# DA14580.net
KiCad netlist of a schematic drawn in Altium Designer
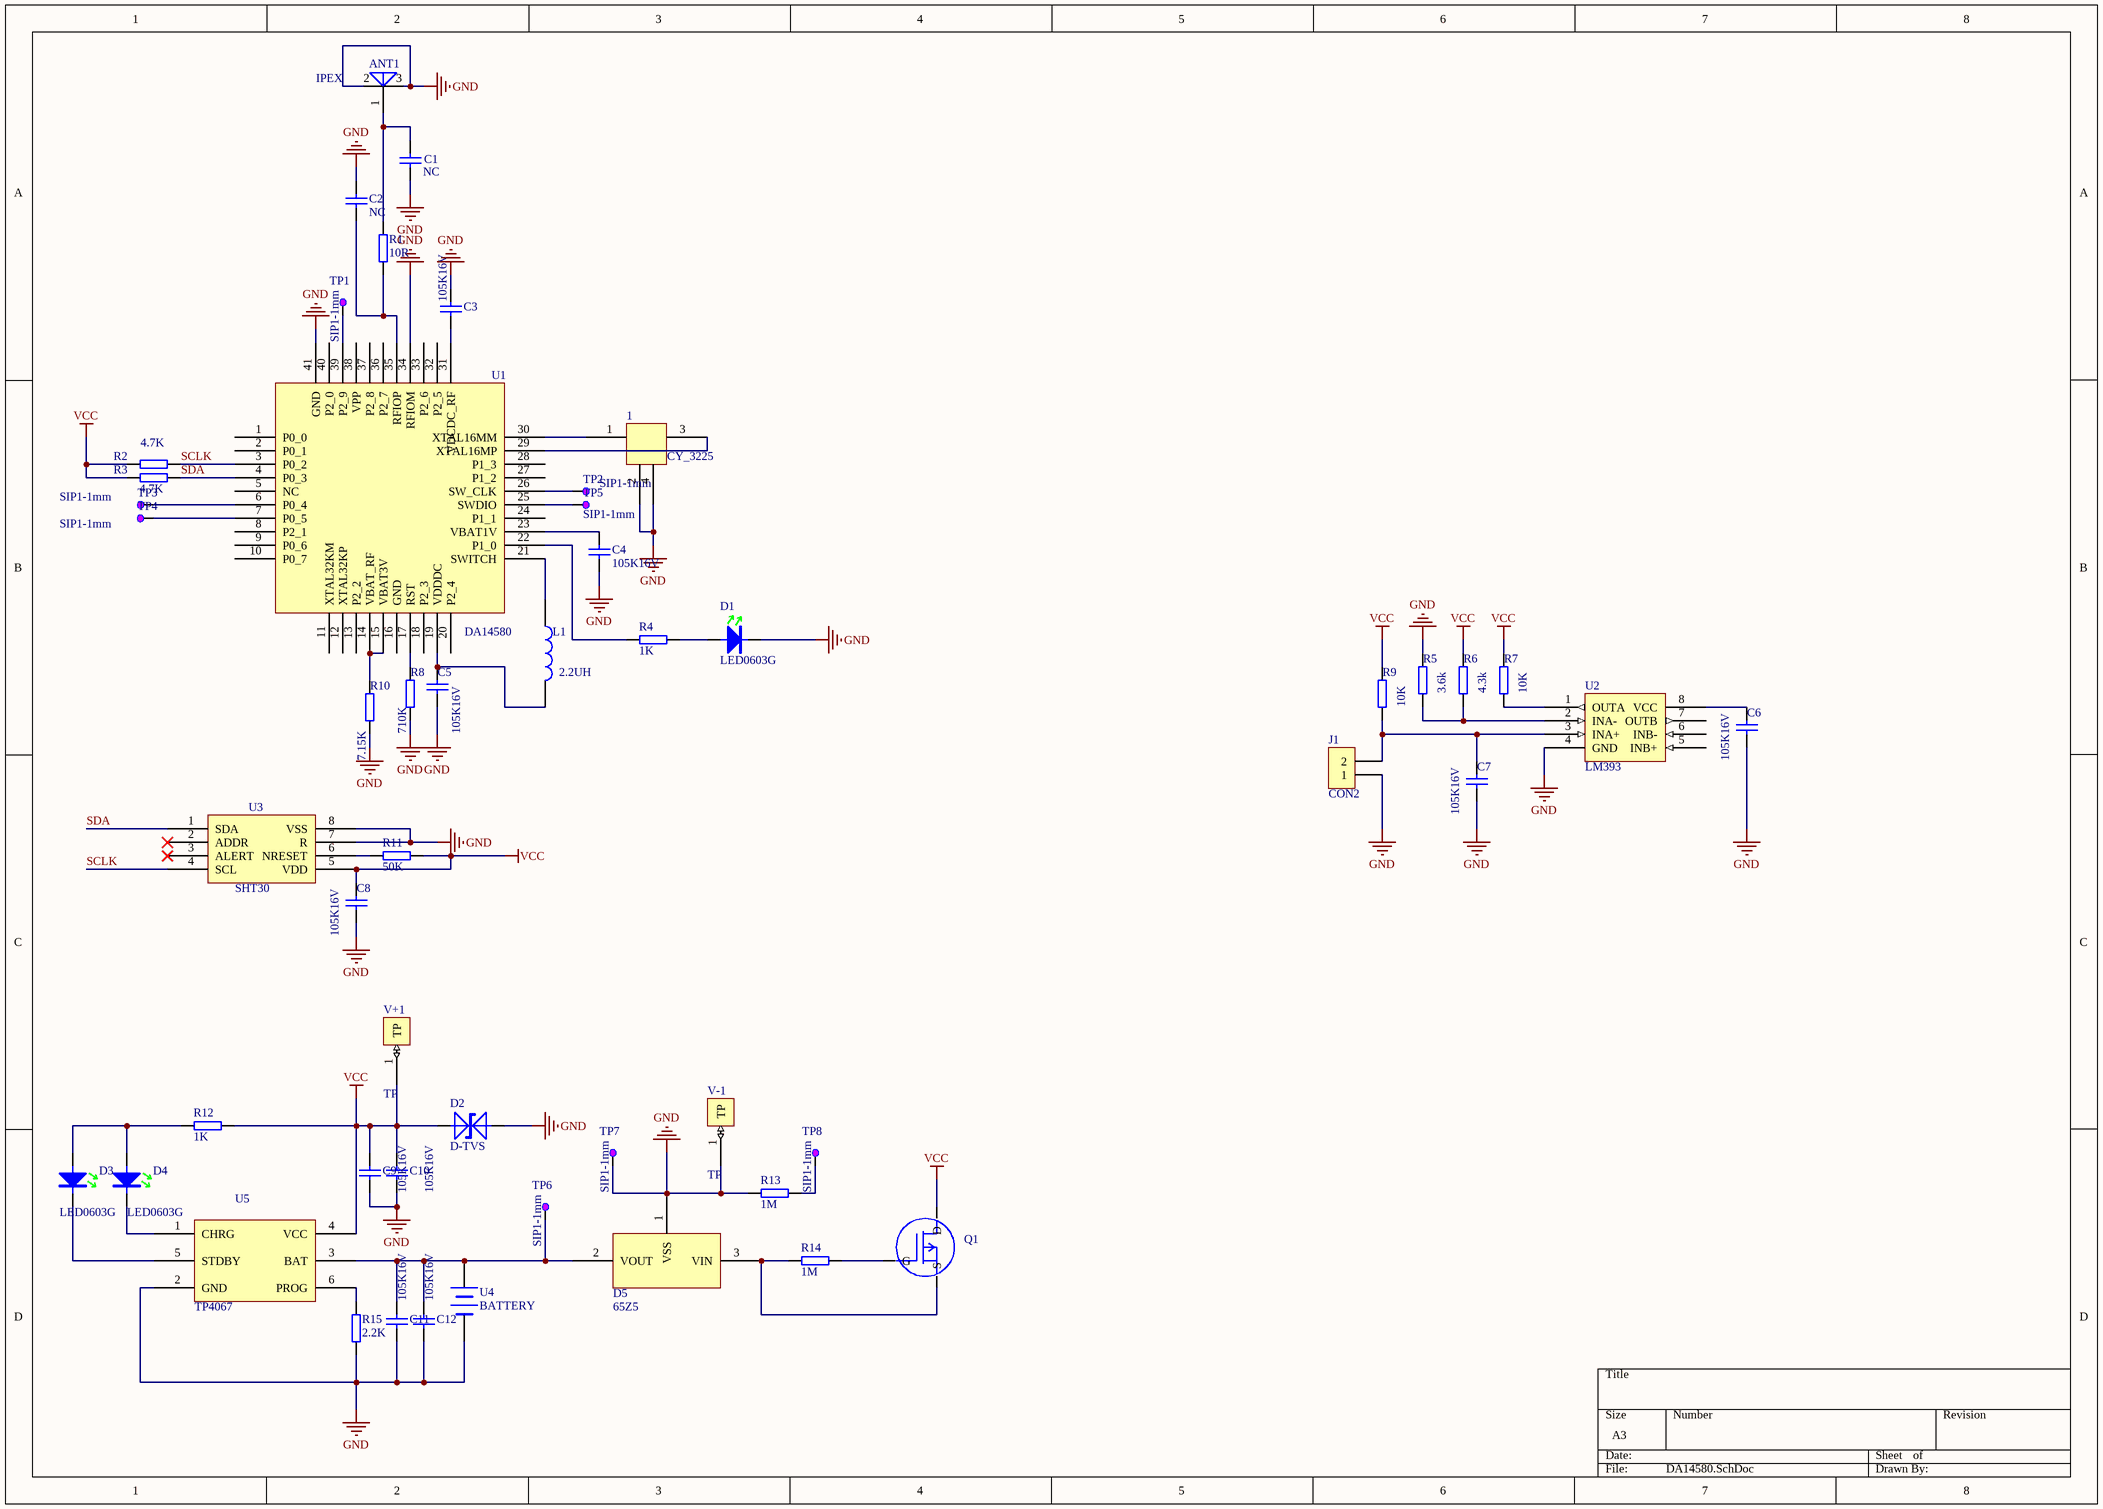
[diagram p0: DA14580.SchDoc]

(export (version "E")
  (design (tool "Eeschema 10.0.6"))
  (components
    (comp (ref "1")
      (value "CY_3225")
      (footprint "CY_3225")
      (libsource (lib "AIWAC-bolsterV01") (part "CY_3225"))
    )
    (comp (ref "ANT1") (value "IPEX") (footprint "IFA") (libsource (lib "AIWAC-bolsterV01") (part "J-IPEX")))
    (comp (ref "C1")
      (value "NC")
      (footprint "C0402")
      (description "贴片电容-陶瓷")
      (libsource (lib "AIWAC-bolsterV01") (part "C0402X7R-101J10V"))
    )
    (comp (ref "C2")
      (value "NC")
      (footprint "C0402")
      (description "贴片电容-陶瓷")
      (libsource (lib "AIWAC-bolsterV01") (part "C0402X7R-101J10V"))
    )
    (comp (ref "C3")
      (value "105K16V")
      (footprint "C0603")
      (description "贴片电容-陶瓷")
      (libsource (lib "AIWAC-bolsterV01") (part "C0603X7R-105K16V"))
    )
    (comp (ref "C4")
      (value "105K16V")
      (footprint "C0603")
      (description "贴片电容-陶瓷")
      (libsource (lib "AIWAC-bolsterV01") (part "C0603X7R-105K16V"))
    )
    (comp (ref "C5")
      (value "105K16V")
      (footprint "C0603")
      (description "贴片电容-陶瓷")
      (libsource (lib "AIWAC-bolsterV01") (part "C0603X7R-105K16V"))
    )
    (comp (ref "C6")
      (value "105K16V")
      (footprint "C0603")
      (description "贴片电容-陶瓷")
      (libsource (lib "AIWAC-bolsterV01") (part "C0603X7R-105K16V"))
    )
    (comp (ref "C7")
      (value "105K16V")
      (footprint "C0603")
      (description "贴片电容-陶瓷")
      (libsource (lib "AIWAC-bolsterV01") (part "C0603X7R-105K16V"))
    )
    (comp (ref "C8")
      (value "105K16V")
      (footprint "C0603")
      (description "贴片电容-陶瓷")
      (libsource (lib "AIWAC-bolsterV01") (part "C0603X7R-105K16V"))
    )
    (comp (ref "C9")
      (value "105K16V")
      (footprint "C0603")
      (description "贴片电容-陶瓷")
      (libsource (lib "AIWAC-bolsterV01") (part "C0603X7R-105K16V"))
    )
    (comp (ref "C10")
      (value "105K16V")
      (footprint "C0603")
      (description "贴片电容-陶瓷")
      (libsource (lib "AIWAC-bolsterV01") (part "C0603X7R-105K16V"))
    )
    (comp (ref "C11")
      (value "105K16V")
      (footprint "C0603")
      (description "贴片电容-陶瓷")
      (libsource (lib "AIWAC-bolsterV01") (part "C0603X7R-105K16V"))
    )
    (comp (ref "C12")
      (value "105K16V")
      (footprint "C0603")
      (description "贴片电容-陶瓷")
      (libsource (lib "AIWAC-bolsterV01") (part "C0603X7R-105K16V"))
    )
    (comp (ref "D1")
      (value "LED0603G")
      (footprint "HS_0603D")
      (description "贴片二极管-LED")
      (libsource (lib "AIWAC-bolsterV01") (part "DLED-0603-G"))
    )
    (comp (ref "D2") (value "D-TVS") (footprint "0603C") (libsource (lib "XU-GENARAL SCH") (part "D-TVS")))
    (comp (ref "D3")
      (value "LED0603G")
      (footprint "HS_0603D")
      (description "贴片二极管-LED")
      (libsource (lib "AIWAC-bolsterV01") (part "DLED-0603-G"))
    )
    (comp (ref "D4")
      (value "LED0603G")
      (footprint "HS_0603D")
      (description "贴片二极管-LED")
      (libsource (lib "AIWAC-bolsterV01") (part "DLED-0603-G"))
    )
    (comp (ref "D5")
      (value "65Z5")
      (footprint "U-SOT-23-3")
      (libsource (lib "AIWAC-bolsterV01") (part "65Z5"))
    )
    (comp (ref "J1")
      (value "CON2")
      (footprint "J-SH1.0-T-1-LT-2A")
      (description "Connector")
      (libsource (lib "AIWAC-bolsterV01") (part "CON2"))
    )
    (comp (ref "L1")
      (value "2.2UH")
      (footprint "0805")
      (libsource (lib "AIWAC-bolsterV01") (part "INDUCTOR"))
    )
    (comp (ref "Q1")
      (value "AO3401 SOT-23")
      (footprint "SOT23-AO3401")
      (description "MOS管")
      (libsource (lib "AIWAC-bolsterV01") (part "2321 SOT-23"))
    )
    (comp (ref "R1")
      (value "10R")
      (footprint "R0402")
      (description "贴片电阻-通用")
      (libsource (lib "AIWAC-bolsterV01") (part "R0402-1KF"))
    )
    (comp (ref "R2")
      (value "4.7K")
      (footprint "R0402")
      (description "贴片电阻-通用")
      (libsource (lib "AIWAC-bolsterV01") (part "R0402-1KF"))
    )
    (comp (ref "R3")
      (value "4.7K")
      (footprint "R0402")
      (description "贴片电阻-通用")
      (libsource (lib "AIWAC-bolsterV01") (part "R0402-1KF"))
    )
    (comp (ref "R4")
      (value "1K")
      (footprint "R0402")
      (description "贴片电阻-通用")
      (libsource (lib "AIWAC-bolsterV01") (part "R0402-1KF"))
    )
    (comp (ref "R5")
      (value "3.6k")
      (footprint "R0402")
      (description "贴片电阻-通用")
      (libsource (lib "AIWAC-bolsterV01") (part "R0402-1KF"))
    )
    (comp (ref "R6")
      (value "4.3k")
      (footprint "R0402")
      (description "贴片电阻-通用")
      (libsource (lib "AIWAC-bolsterV01") (part "R0402-1KF"))
    )
    (comp (ref "R7")
      (value "10K")
      (footprint "R0402")
      (description "贴片电阻-通用")
      (libsource (lib "AIWAC-bolsterV01") (part "R0402-1KF"))
    )
    (comp (ref "R8")
      (value "710K")
      (footprint "R0402")
      (description "贴片电阻-通用")
      (libsource (lib "AIWAC-bolsterV01") (part "R0402-1KF"))
    )
    (comp (ref "R9")
      (value "10K")
      (footprint "R0402")
      (description "贴片电阻-通用")
      (libsource (lib "AIWAC-bolsterV01") (part "R0402-1KF"))
    )
    (comp (ref "R10")
      (value "7.15K")
      (footprint "R0402")
      (description "贴片电阻-通用")
      (libsource (lib "AIWAC-bolsterV01") (part "R0402-1KF"))
    )
    (comp (ref "R11")
      (value "50K")
      (footprint "R0402")
      (description "贴片电阻-通用")
      (libsource (lib "AIWAC-bolsterV01") (part "R0402-1KF"))
    )
    (comp (ref "R12")
      (value "1K")
      (footprint "R0402")
      (description "贴片电阻-通用")
      (libsource (lib "AIWAC-bolsterV01") (part "R0402-1KF"))
    )
    (comp (ref "R13")
      (value "1M")
      (footprint "R0402")
      (description "贴片电阻-通用")
      (libsource (lib "AIWAC-bolsterV01") (part "R0402-1KF"))
    )
    (comp (ref "R14")
      (value "1M")
      (footprint "R0402")
      (description "贴片电阻-通用")
      (libsource (lib "AIWAC-bolsterV01") (part "R0402-1KF"))
    )
    (comp (ref "R15")
      (value "2.2K")
      (footprint "R0402")
      (description "贴片电阻-通用")
      (libsource (lib "AIWAC-bolsterV01") (part "R0402-1KF"))
    )
    (comp (ref "TP1")
      (value "SIP1-1mm")
      (footprint "SIP - 1MM")
      (libsource (lib "AIWAC-bolsterV01") (part "SIP1-2mm"))
    )
    (comp (ref "TP2")
      (value "SIP1-1mm")
      (footprint "SIP - 1MM")
      (libsource (lib "AIWAC-bolsterV01") (part "SIP1-2mm"))
    )
    (comp (ref "TP3")
      (value "SIP1-1mm")
      (footprint "SIP - 1MM")
      (libsource (lib "AIWAC-bolsterV01") (part "SIP1-2mm"))
    )
    (comp (ref "TP4")
      (value "SIP1-1mm")
      (footprint "SIP - 1MM")
      (libsource (lib "AIWAC-bolsterV01") (part "SIP1-2mm"))
    )
    (comp (ref "TP5")
      (value "SIP1-1mm")
      (footprint "SIP - 1MM")
      (libsource (lib "AIWAC-bolsterV01") (part "SIP1-2mm"))
    )
    (comp (ref "TP6")
      (value "SIP1-1mm")
      (footprint "SIP - 1MM")
      (libsource (lib "AIWAC-bolsterV01") (part "SIP1-2mm"))
    )
    (comp (ref "TP7")
      (value "SIP1-1mm")
      (footprint "SIP - 1MM")
      (libsource (lib "AIWAC-bolsterV01") (part "SIP1-2mm"))
    )
    (comp (ref "TP8")
      (value "SIP1-1mm")
      (footprint "SIP - 1MM")
      (libsource (lib "AIWAC-bolsterV01") (part "SIP1-2mm"))
    )
    (comp (ref "U1")
      (value "DA14580")
      (footprint "QFN40P500*500_HS-41N")
      (description "bluetooth")
      (libsource (lib "AIWAC-bolsterV01") (part "DA14580"))
    )
    (comp (ref "U2") (value "LM393") (footprint "SO-8S") (libsource (lib "AIWAC-bolsterV01") (part "LM393")))
    (comp (ref "U3")
      (value "SHT30")
      (footprint "SHT30 DL7DV9")
      (libsource (lib "AIWAC-bolsterV01") (part "SHT30"))
    )
    (comp (ref "U4")
      (value "BATTERY")
      (footprint "BAT 4mm")
      (libsource (lib "HSC32K1(QFN56)_BlueTooth_V2.0_20171108 - 副本") (part "BATTERY"))
    )
    (comp (ref "U5")
      (value "TP4067")
      (footprint "SOT23-6")
      (libsource (lib "AIWAC-bolsterV01") (part "TP4067"))
    )
    (comp (ref "V+1") (value "TP") (footprint "SIP-2MM") (libsource (lib "AIWAC-bolsterV01") (part "TP")))
    (comp (ref "V-1") (value "TP") (footprint "SIP-2MM") (libsource (lib "AIWAC-bolsterV01") (part "TP")))
  )
  (nets
    (net (code "1") (name "/SCLK") (class "Default")
      (node (ref "R2") (pin "1") (pinfunction "1_1") (pintype "passive"))
      (node (ref "U1") (pin "3") (pinfunction "P0_2_3") (pintype "passive"))
      (node (ref "U3") (pin "4") (pinfunction "SCL_4") (pintype "passive"))
    )
    (net (code "2") (name "/SDA") (class "Default")
      (node (ref "R3") (pin "1") (pinfunction "1_1") (pintype "passive"))
      (node (ref "U1") (pin "4") (pinfunction "P0_3_4") (pintype "passive"))
      (node (ref "U3") (pin "1") (pinfunction "SDA_1") (pintype "passive"))
    )
    (net (code "3") (name "GND") (class "Default")
      (node (ref "1") (pin "2") (pinfunction "2_2") (pintype "power_in"))
      (node (ref "1") (pin "4") (pinfunction "4_4") (pintype "power_in"))
      (node (ref "ANT1") (pin "2") (pinfunction "2_2") (pintype "passive"))
      (node (ref "ANT1") (pin "3") (pinfunction "3_3") (pintype "passive"))
      (node (ref "C1") (pin "2") (pinfunction "2_2") (pintype "passive"))
      (node (ref "C10") (pin "2") (pinfunction "2_2") (pintype "passive"))
      (node (ref "C11") (pin "2") (pinfunction "2_2") (pintype "passive"))
      (node (ref "C12") (pin "2") (pinfunction "2_2") (pintype "passive"))
      (node (ref "C2") (pin "1") (pinfunction "1_1") (pintype "passive"))
      (node (ref "C3") (pin "1") (pinfunction "1_1") (pintype "passive"))
      (node (ref "C4") (pin "2") (pinfunction "2_2") (pintype "passive"))
      (node (ref "C5") (pin "2") (pinfunction "2_2") (pintype "passive"))
      (node (ref "C6") (pin "2") (pinfunction "2_2") (pintype "passive"))
      (node (ref "C7") (pin "2") (pinfunction "2_2") (pintype "passive"))
      (node (ref "C8") (pin "2") (pinfunction "2_2") (pintype "passive"))
      (node (ref "C9") (pin "2") (pinfunction "2_2") (pintype "passive"))
      (node (ref "D1") (pin "2") (pinfunction "2_2") (pintype "passive"))
      (node (ref "D2") (pin "1") (pintype "passive"))
      (node (ref "D5") (pin "1") (pinfunction "VSS_1") (pintype "passive"))
      (node (ref "J1") (pin "1") (pinfunction "1_1") (pintype "passive"))
      (node (ref "R10") (pin "1") (pinfunction "1_1") (pintype "passive"))
      (node (ref "R13") (pin "1") (pinfunction "1_1") (pintype "passive"))
      (node (ref "R15") (pin "1") (pinfunction "1_1") (pintype "passive"))
      (node (ref "R5") (pin "2") (pinfunction "2_2") (pintype "passive"))
      (node (ref "R8") (pin "1") (pinfunction "1_1") (pintype "passive"))
      (node (ref "TP7") (pin "1") (pinfunction "1_1") (pintype "passive"))
      (node (ref "U1") (pin "34") (pinfunction "RFIOM_34") (pintype "passive"))
      (node (ref "U1") (pin "41") (pinfunction "GND_41") (pintype "passive"))
      (node (ref "U2") (pin "4") (pinfunction "GND_4") (pintype "power_in"))
      (node (ref "U3") (pin "7") (pinfunction "R_7") (pintype "passive"))
      (node (ref "U3") (pin "8") (pinfunction "VSS_8") (pintype "passive"))
      (node (ref "U4") (pin "2") (pinfunction "-_2") (pintype "passive"))
      (node (ref "U5") (pin "2") (pinfunction "GND_2") (pintype "passive"))
      (node (ref "V-1") (pin "1") (pinfunction "TP_1") (pintype "bidirectional"))
    )
    (net (code "4") (name "Net-(ANT1-W)") (class "Default")
      (node (ref "ANT1") (pin "1") (pinfunction "W_1") (pintype "passive"))
      (node (ref "C1") (pin "1") (pinfunction "1_1") (pintype "passive"))
      (node (ref "R1") (pin "1") (pinfunction "1_1") (pintype "passive"))
    )
    (net (code "5") (name "Net-(D1-Pad1)") (class "Default")
      (node (ref "D1") (pin "1") (pinfunction "1_1") (pintype "passive"))
      (node (ref "R4") (pin "2") (pinfunction "2_2") (pintype "passive"))
    )
    (net (code "6") (name "Net-(D3-Pad1)") (class "Default")
      (node (ref "D3") (pin "1") (pinfunction "1_1") (pintype "passive"))
      (node (ref "D4") (pin "1") (pinfunction "1_1") (pintype "passive"))
      (node (ref "R12") (pin "1") (pinfunction "1_1") (pintype "passive"))
    )
    (net (code "7") (name "Net-(D5-VIN)") (class "Default")
      (node (ref "D5") (pin "3") (pinfunction "VIN_3") (pintype "passive"))
      (node (ref "Q1") (pin "S") (pinfunction "S_S") (pintype "passive"))
      (node (ref "R14") (pin "1") (pinfunction "1_1") (pintype "passive"))
    )
    (net (code "8") (name "Net-(D5-VOUT)") (class "Default")
      (node (ref "C11") (pin "1") (pinfunction "1_1") (pintype "passive"))
      (node (ref "C12") (pin "1") (pinfunction "1_1") (pintype "passive"))
      (node (ref "D5") (pin "2") (pinfunction "VOUT_2") (pintype "passive"))
      (node (ref "TP6") (pin "1") (pinfunction "1_1") (pintype "passive"))
      (node (ref "U4") (pin "1") (pinfunction "+_1") (pintype "passive"))
      (node (ref "U5") (pin "3") (pinfunction "BAT_3") (pintype "passive"))
    )
    (net (code "9") (name "Net-(Q1-PadG)") (class "Default")
      (node (ref "Q1") (pin "G") (pinfunction "G_G") (pintype "passive"))
      (node (ref "R14") (pin "2") (pinfunction "2_2") (pintype "passive"))
    )
    (net (code "10") (name "Net-(R13-Pad2)") (class "Default")
      (node (ref "R13") (pin "2") (pinfunction "2_2") (pintype "passive"))
      (node (ref "TP8") (pin "1") (pinfunction "1_1") (pintype "passive"))
    )
    (net (code "11") (name "Net-(U1-P0_4)") (class "Default")
      (node (ref "TP3") (pin "1") (pinfunction "1_1") (pintype "passive"))
      (node (ref "U1") (pin "6") (pinfunction "P0_4_6") (pintype "passive"))
    )
    (net (code "12") (name "Net-(U1-P0_5)") (class "Default")
      (node (ref "TP4") (pin "1") (pinfunction "1_1") (pintype "passive"))
      (node (ref "U1") (pin "7") (pinfunction "P0_5_7") (pintype "passive"))
    )
    (net (code "13") (name "Net-(U1-P1_0)") (class "Default")
      (node (ref "R4") (pin "1") (pinfunction "1_1") (pintype "passive"))
      (node (ref "U1") (pin "22") (pinfunction "P1_0_22") (pintype "passive"))
    )
    (net (code "14") (name "Net-(U1-P2_9)") (class "Default")
      (node (ref "TP1") (pin "1") (pinfunction "1_1") (pintype "passive"))
      (node (ref "U1") (pin "39") (pinfunction "P2_9_39") (pintype "passive"))
    )
    (net (code "15") (name "Net-(U1-RFIOP)") (class "Default")
      (node (ref "C2") (pin "2") (pinfunction "2_2") (pintype "passive"))
      (node (ref "R1") (pin "2") (pinfunction "2_2") (pintype "passive"))
      (node (ref "U1") (pin "35") (pinfunction "RFIOP_35") (pintype "passive"))
    )
    (net (code "16") (name "Net-(U1-RST)") (class "Default")
      (node (ref "R8") (pin "2") (pinfunction "2_2") (pintype "passive"))
      (node (ref "U1") (pin "17") (pinfunction "RST_17") (pintype "passive"))
    )
    (net (code "17") (name "Net-(U1-SWDIO)") (class "Default")
      (node (ref "TP5") (pin "1") (pinfunction "1_1") (pintype "passive"))
      (node (ref "U1") (pin "25") (pinfunction "SWDIO_25") (pintype "passive"))
    )
    (net (code "18") (name "Net-(U1-SWITCH)") (class "Default")
      (node (ref "L1") (pin "1") (pinfunction "1_1") (pintype "passive"))
      (node (ref "U1") (pin "21") (pinfunction "SWITCH_21") (pintype "passive"))
    )
    (net (code "19") (name "Net-(U1-SW_CLK)") (class "Default")
      (node (ref "TP2") (pin "1") (pinfunction "1_1") (pintype "passive"))
      (node (ref "U1") (pin "26") (pinfunction "SW_CLK_26") (pintype "passive"))
    )
    (net (code "20") (name "Net-(U1-VBAT1V)") (class "Default")
      (node (ref "C4") (pin "1") (pinfunction "1_1") (pintype "passive"))
      (node (ref "U1") (pin "23") (pinfunction "VBAT1V_23") (pintype "passive"))
    )
    (net (code "21") (name "Net-(U1-VBAT3V)") (class "Default")
      (node (ref "R10") (pin "2") (pinfunction "2_2") (pintype "passive"))
      (node (ref "U1") (pin "14") (pinfunction "VBAT_RF_14") (pintype "passive"))
      (node (ref "U1") (pin "15") (pinfunction "VBAT3V_15") (pintype "passive"))
    )
    (net (code "22") (name "Net-(U1-VDCDC_RF)") (class "Default")
      (node (ref "C3") (pin "2") (pinfunction "2_2") (pintype "passive"))
      (node (ref "U1") (pin "31") (pinfunction "VDCDC_RF_31") (pintype "passive"))
    )
    (net (code "23") (name "Net-(U1-VDDDC)") (class "Default")
      (node (ref "C5") (pin "1") (pinfunction "1_1") (pintype "passive"))
      (node (ref "L1") (pin "2") (pinfunction "2_2") (pintype "passive"))
      (node (ref "U1") (pin "19") (pinfunction "VDDDC_19") (pintype "passive"))
    )
    (net (code "24") (name "Net-(U1-XTAL16MM)") (class "Default")
      (node (ref "1") (pin "1") (pinfunction "1_1") (pintype "power_in"))
      (node (ref "U1") (pin "30") (pinfunction "XTAL16MM_30") (pintype "passive"))
    )
    (net (code "25") (name "Net-(U1-XTAL16MP)") (class "Default")
      (node (ref "1") (pin "3") (pinfunction "3_3") (pintype "power_in"))
      (node (ref "U1") (pin "29") (pinfunction "XTAL16MP_29") (pintype "passive"))
    )
    (net (code "26") (name "Net-(U2-INA+)") (class "Default")
      (node (ref "C7") (pin "1") (pinfunction "1_1") (pintype "passive"))
      (node (ref "J1") (pin "2") (pinfunction "2_2") (pintype "passive"))
      (node (ref "R9") (pin "1") (pinfunction "1_1") (pintype "passive"))
      (node (ref "U2") (pin "3") (pinfunction "INA+_3") (pintype "input"))
    )
    (net (code "27") (name "Net-(U2-INA-)") (class "Default")
      (node (ref "R5") (pin "1") (pinfunction "1_1") (pintype "passive"))
      (node (ref "R6") (pin "1") (pinfunction "1_1") (pintype "passive"))
      (node (ref "U2") (pin "2") (pinfunction "INA-_2") (pintype "input"))
    )
    (net (code "28") (name "Net-(U2-OUTA)") (class "Default")
      (node (ref "R7") (pin "1") (pinfunction "1_1") (pintype "passive"))
      (node (ref "U2") (pin "1") (pinfunction "OUTA_1") (pintype "output"))
    )
    (net (code "29") (name "Net-(U2-VCC)") (class "Default")
      (node (ref "C6") (pin "1") (pinfunction "1_1") (pintype "passive"))
      (node (ref "U2") (pin "8") (pinfunction "VCC_8") (pintype "power_in"))
    )
    (net (code "30") (name "Net-(U3-NRESET)") (class "Default")
      (node (ref "R11") (pin "1") (pinfunction "1_1") (pintype "passive"))
      (node (ref "U3") (pin "6") (pinfunction "NRESET_6") (pintype "passive"))
    )
    (net (code "31") (name "Net-(U5-CHRG)") (class "Default")
      (node (ref "D4") (pin "2") (pinfunction "2_2") (pintype "passive"))
      (node (ref "U5") (pin "1") (pinfunction "CHRG_1") (pintype "passive"))
    )
    (net (code "32") (name "Net-(U5-PROG)") (class "Default")
      (node (ref "R15") (pin "2") (pinfunction "2_2") (pintype "passive"))
      (node (ref "U5") (pin "6") (pinfunction "PROG_6") (pintype "passive"))
    )
    (net (code "33") (name "Net-(U5-STDBY)") (class "Default")
      (node (ref "D3") (pin "2") (pinfunction "2_2") (pintype "passive"))
      (node (ref "U5") (pin "5") (pinfunction "STDBY_5") (pintype "passive"))
    )
    (net (code "34") (name "VCC") (class "Default")
      (node (ref "C10") (pin "1") (pinfunction "1_1") (pintype "passive"))
      (node (ref "C8") (pin "1") (pinfunction "1_1") (pintype "passive"))
      (node (ref "C9") (pin "1") (pinfunction "1_1") (pintype "passive"))
      (node (ref "D2") (pin "2") (pintype "passive"))
      (node (ref "Q1") (pin "D") (pinfunction "D_D") (pintype "passive"))
      (node (ref "R11") (pin "2") (pinfunction "2_2") (pintype "passive"))
      (node (ref "R12") (pin "2") (pinfunction "2_2") (pintype "passive"))
      (node (ref "R2") (pin "2") (pinfunction "2_2") (pintype "passive"))
      (node (ref "R3") (pin "2") (pinfunction "2_2") (pintype "passive"))
      (node (ref "R6") (pin "2") (pinfunction "2_2") (pintype "passive"))
      (node (ref "R7") (pin "2") (pinfunction "2_2") (pintype "passive"))
      (node (ref "R9") (pin "2") (pinfunction "2_2") (pintype "passive"))
      (node (ref "U3") (pin "5") (pinfunction "VDD_5") (pintype "passive"))
      (node (ref "U5") (pin "4") (pinfunction "VCC_4") (pintype "passive"))
      (node (ref "V+1") (pin "1") (pinfunction "TP_1") (pintype "bidirectional"))
    )
    (net (code "35") (name "unconnected-(U1-GND-Pad16)") (class "Default")
      (node (ref "U1") (pin "16") (pinfunction "GND_16") (pintype "passive"))
    )
    (net (code "36") (name "unconnected-(U1-NC-Pad5)") (class "Default")
      (node (ref "U1") (pin "5") (pinfunction "NC_5") (pintype "passive"))
    )
    (net (code "37") (name "unconnected-(U1-P0_0-Pad1)") (class "Default")
      (node (ref "U1") (pin "1") (pinfunction "P0_0_1") (pintype "passive"))
    )
    (net (code "38") (name "unconnected-(U1-P0_1-Pad2)") (class "Default")
      (node (ref "U1") (pin "2") (pinfunction "P0_1_2") (pintype "passive"))
    )
    (net (code "39") (name "unconnected-(U1-P0_6-Pad9)") (class "Default")
      (node (ref "U1") (pin "9") (pinfunction "P0_6_9") (pintype "passive"))
    )
    (net (code "40") (name "unconnected-(U1-P0_7-Pad10)") (class "Default")
      (node (ref "U1") (pin "10") (pinfunction "P0_7_10") (pintype "passive"))
    )
    (net (code "41") (name "unconnected-(U1-P1_1-Pad24)") (class "Default")
      (node (ref "U1") (pin "24") (pinfunction "P1_1_24") (pintype "passive"))
    )
    (net (code "42") (name "unconnected-(U1-P1_2-Pad27)") (class "Default")
      (node (ref "U1") (pin "27") (pinfunction "P1_2_27") (pintype "passive"))
    )
    (net (code "43") (name "unconnected-(U1-P1_3-Pad28)") (class "Default")
      (node (ref "U1") (pin "28") (pinfunction "P1_3_28") (pintype "passive"))
    )
    (net (code "44") (name "unconnected-(U1-P2_0-Pad40)") (class "Default")
      (node (ref "U1") (pin "40") (pinfunction "P2_0_40") (pintype "passive"))
    )
    (net (code "45") (name "unconnected-(U1-P2_1-Pad8)") (class "Default")
      (node (ref "U1") (pin "8") (pinfunction "P2_1_8") (pintype "passive"))
    )
    (net (code "46") (name "unconnected-(U1-P2_2-Pad13)") (class "Default")
      (node (ref "U1") (pin "13") (pinfunction "P2_2_13") (pintype "passive"))
    )
    (net (code "47") (name "unconnected-(U1-P2_3-Pad18)") (class "Default")
      (node (ref "U1") (pin "18") (pinfunction "P2_3_18") (pintype "passive"))
    )
    (net (code "48") (name "unconnected-(U1-P2_4-Pad20)") (class "Default")
      (node (ref "U1") (pin "20") (pinfunction "P2_4_20") (pintype "passive"))
    )
    (net (code "49") (name "unconnected-(U1-P2_5-Pad32)") (class "Default")
      (node (ref "U1") (pin "32") (pinfunction "P2_5_32") (pintype "passive"))
    )
    (net (code "50") (name "unconnected-(U1-P2_6-Pad33)") (class "Default")
      (node (ref "U1") (pin "33") (pinfunction "P2_6_33") (pintype "passive"))
    )
    (net (code "51") (name "unconnected-(U1-P2_7-Pad36)") (class "Default")
      (node (ref "U1") (pin "36") (pinfunction "P2_7_36") (pintype "passive"))
    )
    (net (code "52") (name "unconnected-(U1-P2_8-Pad37)") (class "Default")
      (node (ref "U1") (pin "37") (pinfunction "P2_8_37") (pintype "passive"))
    )
    (net (code "53") (name "unconnected-(U1-VPP-Pad38)") (class "Default")
      (node (ref "U1") (pin "38") (pinfunction "VPP_38") (pintype "passive"))
    )
    (net (code "54") (name "unconnected-(U1-XTAL32KM-Pad11)") (class "Default")
      (node (ref "U1") (pin "11") (pinfunction "XTAL32KM_11") (pintype "passive"))
    )
    (net (code "55") (name "unconnected-(U1-XTAL32KP-Pad12)") (class "Default")
      (node (ref "U1") (pin "12") (pinfunction "XTAL32KP_12") (pintype "passive"))
    )
    (net (code "56") (name "unconnected-(U2-INB+-Pad5)") (class "Default")
      (node (ref "U2") (pin "5") (pinfunction "INB+_5") (pintype "input"))
    )
    (net (code "57") (name "unconnected-(U2-INB--Pad6)") (class "Default")
      (node (ref "U2") (pin "6") (pinfunction "INB-_6") (pintype "input"))
    )
    (net (code "58") (name "unconnected-(U2-OUTB-Pad7)") (class "Default")
      (node (ref "U2") (pin "7") (pinfunction "OUTB_7") (pintype "output"))
    )
    (net (code "59") (name "unconnected-(U3-ADDR-Pad2)") (class "Default")
      (node (ref "U3") (pin "2") (pinfunction "ADDR_2") (pintype "passive+no_connect"))
    )
    (net (code "60") (name "unconnected-(U3-ALERT-Pad3)") (class "Default")
      (node (ref "U3") (pin "3") (pinfunction "ALERT_3") (pintype "passive+no_connect"))
    )
  )
)
